# Copter_Transmitter.net
KiCad netlist of a schematic drawn in EAGLE
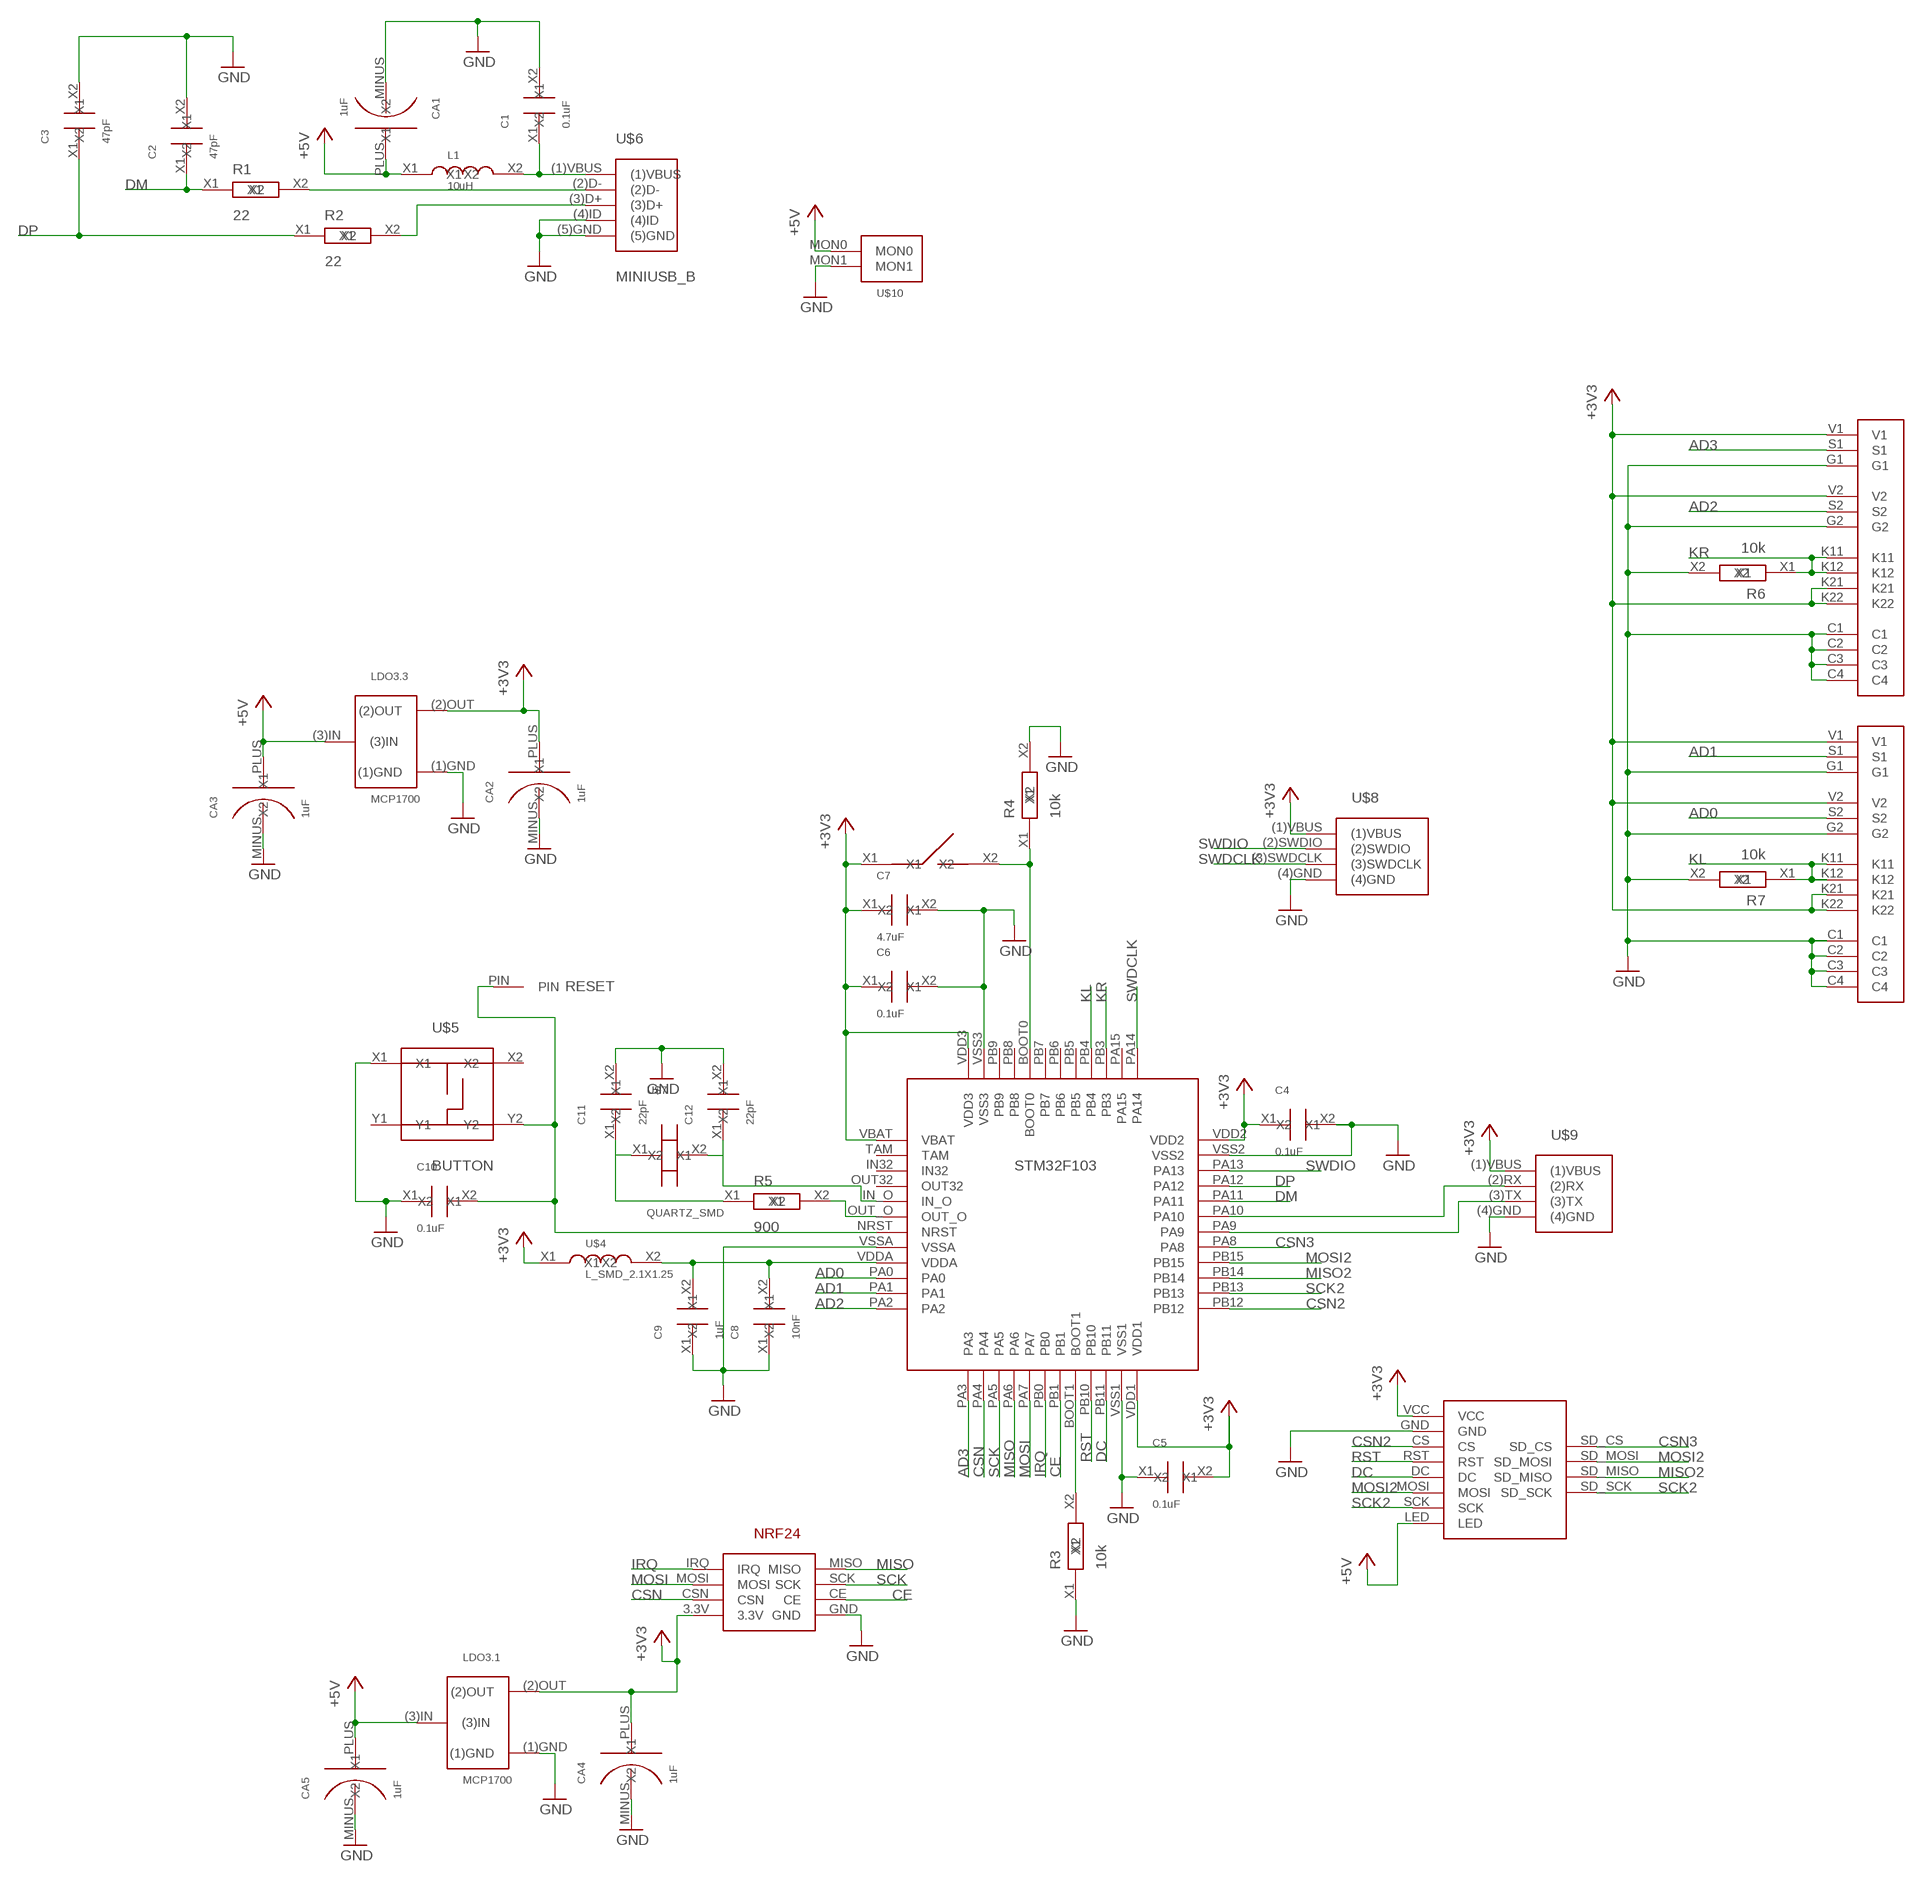
[diagram p0: schematic, sheet 1]

(export (version "E")
  (design (tool "Eeschema 10.0.6"))
  (components
    (comp (ref "C1")
      (value "0.1uF")
      (footprint "eagle-import:SMD_2.1X1.25")
      (libsource (lib "eagle-import") (part "C_SMD_2.1X1.25"))
    )
    (comp (ref "C2")
      (value "47pF")
      (footprint "eagle-import:SMD_2.1X1.25")
      (libsource (lib "eagle-import") (part "C_SMD_2.1X1.25"))
    )
    (comp (ref "C3")
      (value "47pF")
      (footprint "eagle-import:SMD_2.1X1.25")
      (libsource (lib "eagle-import") (part "C_SMD_2.1X1.25"))
    )
    (comp (ref "C4")
      (value "0.1uF")
      (footprint "eagle-import:SMD_2.1X1.25")
      (libsource (lib "eagle-import") (part "C_SMD_2.1X1.25"))
    )
    (comp (ref "C5")
      (value "0.1uF")
      (footprint "eagle-import:SMD_2.1X1.25")
      (libsource (lib "eagle-import") (part "C_SMD_2.1X1.25"))
    )
    (comp (ref "C6")
      (value "0.1uF")
      (footprint "eagle-import:SMD_2.1X1.25")
      (libsource (lib "eagle-import") (part "C_SMD_2.1X1.25"))
    )
    (comp (ref "C7")
      (value "4.7uF")
      (footprint "eagle-import:SMD_2.1X1.25")
      (libsource (lib "eagle-import") (part "C_SMD_2.1X1.25"))
    )
    (comp (ref "C8")
      (value "10nF")
      (footprint "eagle-import:SMD_2.1X1.25")
      (libsource (lib "eagle-import") (part "C_SMD_2.1X1.25"))
    )
    (comp (ref "C9")
      (value "1uF")
      (footprint "eagle-import:SMD_2.1X1.25")
      (libsource (lib "eagle-import") (part "C_SMD_2.1X1.25"))
    )
    (comp (ref "C10")
      (value "0.1uF")
      (footprint "eagle-import:SMD_2.1X1.25")
      (libsource (lib "eagle-import") (part "C_SMD_2.1X1.25"))
    )
    (comp (ref "C11")
      (value "22pF")
      (footprint "eagle-import:SMD_2.1X1.25")
      (libsource (lib "eagle-import") (part "C_SMD_2.1X1.25"))
    )
    (comp (ref "C12")
      (value "22pF")
      (footprint "eagle-import:SMD_2.1X1.25")
      (libsource (lib "eagle-import") (part "C_SMD_2.1X1.25"))
    )
    (comp (ref "CA1")
      (value "1uF")
      (footprint "eagle-import:C_SMD_TA_A")
      (libsource (lib "eagle-import") (part "C_SMD_TA_A"))
    )
    (comp (ref "CA2")
      (value "1uF")
      (footprint "eagle-import:C_SMD_TA_A")
      (libsource (lib "eagle-import") (part "C_SMD_TA_A"))
    )
    (comp (ref "CA3")
      (value "1uF")
      (footprint "eagle-import:C_SMD_TA_A")
      (libsource (lib "eagle-import") (part "C_SMD_TA_A"))
    )
    (comp (ref "CA4")
      (value "1uF")
      (footprint "eagle-import:C_SMD_TA_A")
      (libsource (lib "eagle-import") (part "C_SMD_TA_A"))
    )
    (comp (ref "CA5")
      (value "1uF")
      (footprint "eagle-import:C_SMD_TA_A")
      (libsource (lib "eagle-import") (part "C_SMD_TA_A"))
    )
    (comp (ref "L1")
      (value "10uH")
      (footprint "eagle-import:SMD_2.1X1.25")
      (libsource (lib "eagle-import") (part "L_SMD_2.1X1.25"))
    )
    (comp (ref "LDO3.1")
      (value "MCP1700")
      (footprint "eagle-import:MCP1700")
      (libsource (lib "eagle-import") (part "MCP1700"))
    )
    (comp (ref "LDO3.3")
      (value "MCP1700")
      (footprint "eagle-import:MCP1700")
      (libsource (lib "eagle-import") (part "MCP1700"))
    )
    (comp (ref "R1")
      (value "22")
      (footprint "eagle-import:SMD_2.1X1.25")
      (libsource (lib "eagle-import") (part "R_SMD_2.1X1.25"))
    )
    (comp (ref "R2")
      (value "22")
      (footprint "eagle-import:SMD_2.1X1.25")
      (libsource (lib "eagle-import") (part "R_SMD_2.1X1.25"))
    )
    (comp (ref "R3")
      (value "10k")
      (footprint "eagle-import:SMD_2.1X1.25")
      (libsource (lib "eagle-import") (part "R_SMD_2.1X1.25"))
    )
    (comp (ref "R4")
      (value "10k")
      (footprint "eagle-import:SMD_2.1X1.25")
      (libsource (lib "eagle-import") (part "R_SMD_2.1X1.25"))
    )
    (comp (ref "R5")
      (value "900")
      (footprint "eagle-import:SMD_2.1X1.25")
      (libsource (lib "eagle-import") (part "R_SMD_2.1X1.25"))
    )
    (comp (ref "R6")
      (value "10k")
      (footprint "eagle-import:SMD_2.1X1.25")
      (libsource (lib "eagle-import") (part "R_SMD_2.1X1.25"))
    )
    (comp (ref "R7")
      (value "10k")
      (footprint "eagle-import:SMD_2.1X1.25")
      (libsource (lib "eagle-import") (part "R_SMD_2.1X1.25"))
    )
    (comp (ref "RESET")
      (value "PIN")
      (footprint "eagle-import:PIN")
      (libsource (lib "eagle-import") (part "PIN"))
    )
    (comp (ref "STM32F103")
      (value "STM32F103CBT6")
      (footprint "eagle-import:STM32F103CBT6")
      (libsource (lib "eagle-import") (part "STM32F103CBT6"))
    )
    (comp (ref "U$1")
      (value "TFT1.8_SD")
      (footprint "eagle-import:TFT1.8_SD")
      (libsource (lib "eagle-import") (part "TFT1.8_SD"))
    )
    (comp (ref "U$2")
      (value "NRF24_PLUG")
      (footprint "eagle-import:NRF24_PLUG")
      (libsource (lib "eagle-import") (part "NRF24_PLUG"))
    )
    (comp (ref "U$3")
      (value "DIP_1")
      (footprint "eagle-import:DIP_1")
      (libsource (lib "eagle-import") (part "DIP_1"))
    )
    (comp (ref "U$4")
      (value "L_SMD_2.1X1.25")
      (footprint "eagle-import:SMD_2.1X1.25")
      (libsource (lib "eagle-import") (part "L_SMD_2.1X1.25"))
    )
    (comp (ref "U$5")
      (value "BUTTON")
      (footprint "eagle-import:BUTTON")
      (libsource (lib "eagle-import") (part "BUTTON"))
    )
    (comp (ref "U$6")
      (value "MINIUSB_B")
      (footprint "eagle-import:MINIUSB_B")
      (libsource (lib "eagle-import") (part "MINIUSB_B"))
    )
    (comp (ref "U$7")
      (value "QUARTZ_SMD")
      (footprint "eagle-import:QUARTZ_SMD")
      (libsource (lib "eagle-import") (part "QUARTZ_SMD"))
    )
    (comp (ref "U$8")
      (value "SWD")
      (footprint "eagle-import:SWD")
      (libsource (lib "eagle-import") (part "SWD"))
    )
    (comp (ref "U$9")
      (value "USART")
      (footprint "eagle-import:USART")
      (libsource (lib "eagle-import") (part "USART"))
    )
    (comp (ref "U$10")
      (value "MON2PIN")
      (footprint "eagle-import:MON2PIN")
      (libsource (lib "eagle-import") (part "MON2PIN"))
    )
    (comp (ref "U$11")
      (value "JOYSTICK_MINI")
      (footprint "eagle-import:JOYSTICK_MINI")
      (libsource (lib "eagle-import") (part "JOYSTICK_MINI"))
    )
    (comp (ref "U$12")
      (value "JOYSTICK_MINI")
      (footprint "eagle-import:JOYSTICK_MINI")
      (libsource (lib "eagle-import") (part "JOYSTICK_MINI"))
    )
  )
  (nets
    (net (code "1") (name "+3V3") (class "Default")
      (node (ref "C4") (pin "X1") (pinfunction "X1_X1") (pintype "bidirectional"))
      (node (ref "C5") (pin "X2") (pinfunction "X2_X2") (pintype "bidirectional"))
      (node (ref "C6") (pin "X1") (pinfunction "X1_X1") (pintype "bidirectional"))
      (node (ref "C7") (pin "X1") (pinfunction "X1_X1") (pintype "bidirectional"))
      (node (ref "CA2") (pin "PLUS") (pinfunction "X2_PLUS") (pintype "bidirectional"))
      (node (ref "CA4") (pin "PLUS") (pinfunction "X2_PLUS") (pintype "bidirectional"))
      (node (ref "LDO3.1") (pin "(2)OUT") (pinfunction "(2)OUT_(2)OUT") (pintype "bidirectional"))
      (node (ref "LDO3.3") (pin "(2)OUT") (pinfunction "(2)OUT_(2)OUT") (pintype "bidirectional"))
      (node (ref "STM32F103") (pin "VBAT") (pinfunction "VBAT_VBAT") (pintype "bidirectional"))
      (node (ref "STM32F103") (pin "VDD1") (pinfunction "VDD1_VDD1") (pintype "bidirectional"))
      (node (ref "STM32F103") (pin "VDD2") (pinfunction "VDD2_VDD2") (pintype "bidirectional"))
      (node (ref "STM32F103") (pin "VDD3") (pinfunction "VDD3_VDD3") (pintype "bidirectional"))
      (node (ref "U$1") (pin "VCC") (pinfunction "VCC_VCC") (pintype "bidirectional"))
      (node (ref "U$11") (pin "K21") (pinfunction "K21_K21") (pintype "bidirectional"))
      (node (ref "U$11") (pin "K22") (pinfunction "K22_K22") (pintype "bidirectional"))
      (node (ref "U$11") (pin "V1") (pinfunction "V1_V1") (pintype "bidirectional"))
      (node (ref "U$11") (pin "V2") (pinfunction "V2_V2") (pintype "bidirectional"))
      (node (ref "U$12") (pin "K21") (pinfunction "K21_K21") (pintype "bidirectional"))
      (node (ref "U$12") (pin "K22") (pinfunction "K22_K22") (pintype "bidirectional"))
      (node (ref "U$12") (pin "V1") (pinfunction "V1_V1") (pintype "bidirectional"))
      (node (ref "U$12") (pin "V2") (pinfunction "V2_V2") (pintype "bidirectional"))
      (node (ref "U$2") (pin "3.3V") (pinfunction "3.3V_3.3V") (pintype "bidirectional"))
      (node (ref "U$3") (pin "X1") (pinfunction "X1_X1") (pintype "bidirectional"))
      (node (ref "U$4") (pin "X1") (pinfunction "X1_X1") (pintype "bidirectional"))
      (node (ref "U$8") (pin "(1)VBUS") (pinfunction "(1)VBUS_(1)VBUS") (pintype "bidirectional"))
      (node (ref "U$9") (pin "(1)VBUS") (pinfunction "(1)VBUS_(1)VBUS") (pintype "bidirectional"))
    )
    (net (code "2") (name "+5V") (class "Default")
      (node (ref "CA1") (pin "PLUS") (pinfunction "X2_PLUS") (pintype "bidirectional"))
      (node (ref "CA3") (pin "PLUS") (pinfunction "X2_PLUS") (pintype "bidirectional"))
      (node (ref "CA5") (pin "PLUS") (pinfunction "X2_PLUS") (pintype "bidirectional"))
      (node (ref "L1") (pin "X1") (pinfunction "X1_X1") (pintype "bidirectional"))
      (node (ref "LDO3.1") (pin "(3)IN") (pinfunction "(3)IN_(3)IN") (pintype "bidirectional"))
      (node (ref "LDO3.3") (pin "(3)IN") (pinfunction "(3)IN_(3)IN") (pintype "bidirectional"))
      (node (ref "U$1") (pin "LED") (pinfunction "LED_LED") (pintype "bidirectional"))
      (node (ref "U$10") (pin "MON0") (pinfunction "MON0_MON0") (pintype "bidirectional"))
    )
    (net (code "3") (name "/AD0") (class "Default")
      (node (ref "STM32F103") (pin "PA0") (pinfunction "PA0_PA0") (pintype "bidirectional"))
      (node (ref "U$11") (pin "S2") (pinfunction "S2_S2") (pintype "bidirectional"))
    )
    (net (code "4") (name "/AD1") (class "Default")
      (node (ref "STM32F103") (pin "PA1") (pinfunction "PA1_PA1") (pintype "bidirectional"))
      (node (ref "U$11") (pin "S1") (pinfunction "S1_S1") (pintype "bidirectional"))
    )
    (net (code "5") (name "/AD2") (class "Default")
      (node (ref "STM32F103") (pin "PA2") (pinfunction "PA2_PA2") (pintype "bidirectional"))
      (node (ref "U$12") (pin "S2") (pinfunction "S2_S2") (pintype "bidirectional"))
    )
    (net (code "6") (name "/AD3") (class "Default")
      (node (ref "STM32F103") (pin "PA3") (pinfunction "PA3_PA3") (pintype "bidirectional"))
      (node (ref "U$12") (pin "S1") (pinfunction "S1_S1") (pintype "bidirectional"))
    )
    (net (code "7") (name "/CE") (class "Default")
      (node (ref "STM32F103") (pin "PB1") (pinfunction "PB1_PB1") (pintype "bidirectional"))
      (node (ref "U$2") (pin "CE") (pinfunction "CE_CE") (pintype "bidirectional"))
    )
    (net (code "8") (name "/CSN") (class "Default")
      (node (ref "STM32F103") (pin "PA4") (pinfunction "PA4_PA4") (pintype "bidirectional"))
      (node (ref "U$2") (pin "CSN") (pinfunction "CSN_CSN") (pintype "bidirectional"))
    )
    (net (code "9") (name "/CSN2") (class "Default")
      (node (ref "STM32F103") (pin "PB12") (pinfunction "PB12_PB12") (pintype "bidirectional"))
      (node (ref "U$1") (pin "CS") (pinfunction "CS_CS") (pintype "bidirectional"))
    )
    (net (code "10") (name "/CSN3") (class "Default")
      (node (ref "STM32F103") (pin "PA8") (pinfunction "PA8_PA8") (pintype "bidirectional"))
      (node (ref "U$1") (pin "SD_CS") (pinfunction "SD_CS_SD_CS") (pintype "bidirectional"))
    )
    (net (code "11") (name "/DC") (class "Default")
      (node (ref "STM32F103") (pin "PB11") (pinfunction "PB11_PB11") (pintype "bidirectional"))
      (node (ref "U$1") (pin "DC") (pinfunction "DC_DC") (pintype "bidirectional"))
    )
    (net (code "12") (name "/DM") (class "Default")
      (node (ref "C2") (pin "X1") (pinfunction "X1_X1") (pintype "bidirectional"))
      (node (ref "R1") (pin "X1") (pinfunction "X1_X1") (pintype "bidirectional"))
      (node (ref "STM32F103") (pin "PA11") (pinfunction "PA11_PA11") (pintype "bidirectional"))
    )
    (net (code "13") (name "/DP") (class "Default")
      (node (ref "C3") (pin "X1") (pinfunction "X1_X1") (pintype "bidirectional"))
      (node (ref "R2") (pin "X1") (pinfunction "X1_X1") (pintype "bidirectional"))
      (node (ref "STM32F103") (pin "PA12") (pinfunction "PA12_PA12") (pintype "bidirectional"))
    )
    (net (code "14") (name "/IRQ") (class "Default")
      (node (ref "STM32F103") (pin "PB0") (pinfunction "PB0_PB0") (pintype "bidirectional"))
      (node (ref "U$2") (pin "IRQ") (pinfunction "IRQ_IRQ") (pintype "bidirectional"))
    )
    (net (code "15") (name "/KL") (class "Default")
      (node (ref "R7") (pin "X1") (pinfunction "X1_X1") (pintype "bidirectional"))
      (node (ref "STM32F103") (pin "PB4") (pinfunction "PB4_PB4") (pintype "bidirectional"))
      (node (ref "U$11") (pin "K11") (pinfunction "K11_K11") (pintype "bidirectional"))
      (node (ref "U$11") (pin "K12") (pinfunction "K12_K12") (pintype "bidirectional"))
    )
    (net (code "16") (name "/KR") (class "Default")
      (node (ref "R6") (pin "X1") (pinfunction "X1_X1") (pintype "bidirectional"))
      (node (ref "STM32F103") (pin "PB3") (pinfunction "PB3_PB3") (pintype "bidirectional"))
      (node (ref "U$12") (pin "K11") (pinfunction "K11_K11") (pintype "bidirectional"))
      (node (ref "U$12") (pin "K12") (pinfunction "K12_K12") (pintype "bidirectional"))
    )
    (net (code "17") (name "/MISO") (class "Default")
      (node (ref "STM32F103") (pin "PA6") (pinfunction "PA6_PA6") (pintype "bidirectional"))
      (node (ref "U$2") (pin "MISO") (pinfunction "MISO_MISO") (pintype "bidirectional"))
    )
    (net (code "18") (name "/MISO2") (class "Default")
      (node (ref "STM32F103") (pin "PB14") (pinfunction "PB14_PB14") (pintype "bidirectional"))
      (node (ref "U$1") (pin "SD_MISO") (pinfunction "SD_MISO_SD_MISO") (pintype "bidirectional"))
    )
    (net (code "19") (name "/MOSI") (class "Default")
      (node (ref "STM32F103") (pin "PA7") (pinfunction "PA7_PA7") (pintype "bidirectional"))
      (node (ref "U$2") (pin "MOSI") (pinfunction "MOSI_MOSI") (pintype "bidirectional"))
    )
    (net (code "20") (name "/MOSI2") (class "Default")
      (node (ref "STM32F103") (pin "PB15") (pinfunction "PB15_PB15") (pintype "bidirectional"))
      (node (ref "U$1") (pin "MOSI") (pinfunction "MOSI_MOSI") (pintype "bidirectional"))
      (node (ref "U$1") (pin "SD_MOSI") (pinfunction "SD_MOSI_SD_MOSI") (pintype "bidirectional"))
    )
    (net (code "21") (name "/RST") (class "Default")
      (node (ref "STM32F103") (pin "PB10") (pinfunction "PB10_PB10") (pintype "bidirectional"))
      (node (ref "U$1") (pin "RST") (pinfunction "RST_RST") (pintype "bidirectional"))
    )
    (net (code "22") (name "/SCK") (class "Default")
      (node (ref "STM32F103") (pin "PA5") (pinfunction "PA5_PA5") (pintype "bidirectional"))
      (node (ref "U$2") (pin "SCK") (pinfunction "SCK_SCK") (pintype "bidirectional"))
    )
    (net (code "23") (name "/SCK2") (class "Default")
      (node (ref "STM32F103") (pin "PB13") (pinfunction "PB13_PB13") (pintype "bidirectional"))
      (node (ref "U$1") (pin "SCK") (pinfunction "SCK_SCK") (pintype "bidirectional"))
      (node (ref "U$1") (pin "SD_SCK") (pinfunction "SD_SCK_SD_SCK") (pintype "bidirectional"))
    )
    (net (code "24") (name "/SWDCLK") (class "Default")
      (node (ref "STM32F103") (pin "PA14") (pinfunction "PA14_PA14") (pintype "bidirectional"))
      (node (ref "U$8") (pin "(3)SWDCLK") (pinfunction "(3)SWDCLK_(3)SWDCLK") (pintype "bidirectional"))
    )
    (net (code "25") (name "/SWDIO") (class "Default")
      (node (ref "STM32F103") (pin "PA13") (pinfunction "PA13_PA13") (pintype "bidirectional"))
      (node (ref "U$8") (pin "(2)SWDIO") (pinfunction "(2)SWDIO_(2)SWDIO") (pintype "bidirectional"))
    )
    (net (code "26") (name "GND") (class "Default")
      (node (ref "C1") (pin "X2") (pinfunction "X2_X2") (pintype "bidirectional"))
      (node (ref "C10") (pin "X1") (pinfunction "X1_X1") (pintype "bidirectional"))
      (node (ref "C11") (pin "X2") (pinfunction "X2_X2") (pintype "bidirectional"))
      (node (ref "C12") (pin "X2") (pinfunction "X2_X2") (pintype "bidirectional"))
      (node (ref "C2") (pin "X2") (pinfunction "X2_X2") (pintype "bidirectional"))
      (node (ref "C3") (pin "X2") (pinfunction "X2_X2") (pintype "bidirectional"))
      (node (ref "C4") (pin "X2") (pinfunction "X2_X2") (pintype "bidirectional"))
      (node (ref "C5") (pin "X1") (pinfunction "X1_X1") (pintype "bidirectional"))
      (node (ref "C6") (pin "X2") (pinfunction "X2_X2") (pintype "bidirectional"))
      (node (ref "C7") (pin "X2") (pinfunction "X2_X2") (pintype "bidirectional"))
      (node (ref "C8") (pin "X1") (pinfunction "X1_X1") (pintype "bidirectional"))
      (node (ref "C9") (pin "X1") (pinfunction "X1_X1") (pintype "bidirectional"))
      (node (ref "CA1") (pin "MINUS") (pinfunction "X1_MINUS") (pintype "bidirectional"))
      (node (ref "CA2") (pin "MINUS") (pinfunction "X1_MINUS") (pintype "bidirectional"))
      (node (ref "CA3") (pin "MINUS") (pinfunction "X1_MINUS") (pintype "bidirectional"))
      (node (ref "CA4") (pin "MINUS") (pinfunction "X1_MINUS") (pintype "bidirectional"))
      (node (ref "CA5") (pin "MINUS") (pinfunction "X1_MINUS") (pintype "bidirectional"))
      (node (ref "LDO3.1") (pin "(1)GND") (pinfunction "(1)GND_(1)GND") (pintype "bidirectional"))
      (node (ref "LDO3.3") (pin "(1)GND") (pinfunction "(1)GND_(1)GND") (pintype "bidirectional"))
      (node (ref "R3") (pin "X1") (pinfunction "X1_X1") (pintype "bidirectional"))
      (node (ref "R4") (pin "X2") (pinfunction "X2_X2") (pintype "bidirectional"))
      (node (ref "R6") (pin "X2") (pinfunction "X2_X2") (pintype "bidirectional"))
      (node (ref "R7") (pin "X2") (pinfunction "X2_X2") (pintype "bidirectional"))
      (node (ref "STM32F103") (pin "VSS1") (pinfunction "VSS1_VSS1") (pintype "bidirectional"))
      (node (ref "STM32F103") (pin "VSS2") (pinfunction "VSS2_VSS2") (pintype "bidirectional"))
      (node (ref "STM32F103") (pin "VSS3") (pinfunction "VSS3_VSS3") (pintype "bidirectional"))
      (node (ref "STM32F103") (pin "VSSA") (pinfunction "VSSA_VSSA") (pintype "bidirectional"))
      (node (ref "U$1") (pin "GND") (pinfunction "GND_GND") (pintype "bidirectional"))
      (node (ref "U$10") (pin "MON1") (pinfunction "MON1_MON1") (pintype "bidirectional"))
      (node (ref "U$11") (pin "C1") (pinfunction "C1_C1") (pintype "bidirectional"))
      (node (ref "U$11") (pin "C2") (pinfunction "C2_C2") (pintype "bidirectional"))
      (node (ref "U$11") (pin "C3") (pinfunction "C3_C3") (pintype "bidirectional"))
      (node (ref "U$11") (pin "C4") (pinfunction "C4_C4") (pintype "bidirectional"))
      (node (ref "U$11") (pin "G1") (pinfunction "G1_G1") (pintype "bidirectional"))
      (node (ref "U$11") (pin "G2") (pinfunction "G2_G2") (pintype "bidirectional"))
      (node (ref "U$12") (pin "C1") (pinfunction "C1_C1") (pintype "bidirectional"))
      (node (ref "U$12") (pin "C2") (pinfunction "C2_C2") (pintype "bidirectional"))
      (node (ref "U$12") (pin "C3") (pinfunction "C3_C3") (pintype "bidirectional"))
      (node (ref "U$12") (pin "C4") (pinfunction "C4_C4") (pintype "bidirectional"))
      (node (ref "U$12") (pin "G1") (pinfunction "G1_G1") (pintype "bidirectional"))
      (node (ref "U$12") (pin "G2") (pinfunction "G2_G2") (pintype "bidirectional"))
      (node (ref "U$2") (pin "GND") (pinfunction "GND_GND") (pintype "bidirectional"))
      (node (ref "U$5") (pin "X1") (pinfunction "X1_X1") (pintype "bidirectional"))
      (node (ref "U$6") (pin "(4)ID") (pinfunction "(4)ID_(4)ID") (pintype "bidirectional"))
      (node (ref "U$6") (pin "(5)GND") (pinfunction "(5)GND_(5)GND") (pintype "bidirectional"))
      (node (ref "U$8") (pin "(4)GND") (pinfunction "(4)GND_(4)GND") (pintype "bidirectional"))
      (node (ref "U$9") (pin "(4)GND") (pinfunction "(4)GND_(4)GND") (pintype "bidirectional"))
    )
    (net (code "27") (name "Net-(C1-PadX1)") (class "Default")
      (node (ref "C1") (pin "X1") (pinfunction "X1_X1") (pintype "bidirectional"))
      (node (ref "L1") (pin "X2") (pinfunction "X2_X2") (pintype "bidirectional"))
      (node (ref "U$6") (pin "(1)VBUS") (pinfunction "(1)VBUS_(1)VBUS") (pintype "bidirectional"))
    )
    (net (code "28") (name "Net-(C8-PadX2)") (class "Default")
      (node (ref "C8") (pin "X2") (pinfunction "X2_X2") (pintype "bidirectional"))
      (node (ref "C9") (pin "X2") (pinfunction "X2_X2") (pintype "bidirectional"))
      (node (ref "STM32F103") (pin "VDDA") (pinfunction "VDDA_VDDA") (pintype "bidirectional"))
      (node (ref "U$4") (pin "X2") (pinfunction "X2_X2") (pintype "bidirectional"))
    )
    (net (code "29") (name "Net-(C10-PadX2)") (class "Default")
      (node (ref "C10") (pin "X2") (pinfunction "X2_X2") (pintype "bidirectional"))
      (node (ref "RESET") (pin "PIN") (pinfunction "PIN_PIN") (pintype "bidirectional"))
      (node (ref "STM32F103") (pin "NRST") (pinfunction "NRST_NRST") (pintype "bidirectional"))
      (node (ref "U$5") (pin "Y2") (pinfunction "Y2_Y2") (pintype "bidirectional"))
    )
    (net (code "30") (name "Net-(C11-PadX1)") (class "Default")
      (node (ref "C11") (pin "X1") (pinfunction "X1_X1") (pintype "bidirectional"))
      (node (ref "R5") (pin "X1") (pinfunction "X1_X1") (pintype "bidirectional"))
      (node (ref "U$7") (pin "X1") (pinfunction "X1_X1") (pintype "bidirectional"))
    )
    (net (code "31") (name "Net-(C12-PadX1)") (class "Default")
      (node (ref "C12") (pin "X1") (pinfunction "X1_X1") (pintype "bidirectional"))
      (node (ref "STM32F103") (pin "IN_O") (pinfunction "IN_O_IN_O") (pintype "bidirectional"))
      (node (ref "U$7") (pin "X2") (pinfunction "X2_X2") (pintype "bidirectional"))
    )
    (net (code "32") (name "Net-(R1-PadX2)") (class "Default")
      (node (ref "R1") (pin "X2") (pinfunction "X2_X2") (pintype "bidirectional"))
      (node (ref "U$6") (pin "(2)D-") (pinfunction "(2)D-_(2)D-") (pintype "bidirectional"))
    )
    (net (code "33") (name "Net-(R2-PadX2)") (class "Default")
      (node (ref "R2") (pin "X2") (pinfunction "X2_X2") (pintype "bidirectional"))
      (node (ref "U$6") (pin "(3)D+") (pinfunction "(3)D+_(3)D+") (pintype "bidirectional"))
    )
    (net (code "34") (name "Net-(R3-PadX2)") (class "Default")
      (node (ref "R3") (pin "X2") (pinfunction "X2_X2") (pintype "bidirectional"))
      (node (ref "STM32F103") (pin "BOOT1") (pinfunction "BOOT1_BOOT1") (pintype "bidirectional"))
    )
    (net (code "35") (name "Net-(R4-PadX1)") (class "Default")
      (node (ref "R4") (pin "X1") (pinfunction "X1_X1") (pintype "bidirectional"))
      (node (ref "STM32F103") (pin "BOOT0") (pinfunction "BOOT0_BOOT0") (pintype "bidirectional"))
      (node (ref "U$3") (pin "X2") (pinfunction "X2_X2") (pintype "bidirectional"))
    )
    (net (code "36") (name "Net-(R5-PadX2)") (class "Default")
      (node (ref "R5") (pin "X2") (pinfunction "X2_X2") (pintype "bidirectional"))
      (node (ref "STM32F103") (pin "OUT_O") (pinfunction "OUT_O_OUT_O") (pintype "bidirectional"))
    )
    (net (code "37") (name "Net-(STM32F103-PadPA9)") (class "Default")
      (node (ref "STM32F103") (pin "PA9") (pinfunction "PA9_PA9") (pintype "bidirectional"))
      (node (ref "U$9") (pin "(3)TX") (pinfunction "(3)TX_(3)TX") (pintype "bidirectional"))
    )
    (net (code "38") (name "Net-(STM32F103-PadPA10)") (class "Default")
      (node (ref "STM32F103") (pin "PA10") (pinfunction "PA10_PA10") (pintype "bidirectional"))
      (node (ref "U$9") (pin "(2)RX") (pinfunction "(2)RX_(2)RX") (pintype "bidirectional"))
    )
    (net (code "39") (name "unconnected-(STM32F103-PadIN32)") (class "Default")
      (node (ref "STM32F103") (pin "IN32") (pinfunction "IN32_IN32") (pintype "bidirectional"))
    )
    (net (code "40") (name "unconnected-(STM32F103-PadOUT32)") (class "Default")
      (node (ref "STM32F103") (pin "OUT32") (pinfunction "OUT32_OUT32") (pintype "bidirectional"))
    )
    (net (code "41") (name "unconnected-(STM32F103-PadPA15)") (class "Default")
      (node (ref "STM32F103") (pin "PA15") (pinfunction "PA15_PA15") (pintype "bidirectional"))
    )
    (net (code "42") (name "unconnected-(STM32F103-PadPB5)") (class "Default")
      (node (ref "STM32F103") (pin "PB5") (pinfunction "PB5_PB5") (pintype "bidirectional"))
    )
    (net (code "43") (name "unconnected-(STM32F103-PadPB6)") (class "Default")
      (node (ref "STM32F103") (pin "PB6") (pinfunction "PB6_PB6") (pintype "bidirectional"))
    )
    (net (code "44") (name "unconnected-(STM32F103-PadPB7)") (class "Default")
      (node (ref "STM32F103") (pin "PB7") (pinfunction "PB7_PB7") (pintype "bidirectional"))
    )
    (net (code "45") (name "unconnected-(STM32F103-PadPB8)") (class "Default")
      (node (ref "STM32F103") (pin "PB8") (pinfunction "PB8_PB8") (pintype "bidirectional"))
    )
    (net (code "46") (name "unconnected-(STM32F103-PadPB9)") (class "Default")
      (node (ref "STM32F103") (pin "PB9") (pinfunction "PB9_PB9") (pintype "bidirectional"))
    )
    (net (code "47") (name "unconnected-(STM32F103-PadTAM)") (class "Default")
      (node (ref "STM32F103") (pin "TAM") (pinfunction "TAM_TAM") (pintype "bidirectional"))
    )
    (net (code "48") (name "unconnected-(U$5-PadX2)") (class "Default")
      (node (ref "U$5") (pin "X2") (pinfunction "X2_X2") (pintype "bidirectional"))
    )
    (net (code "49") (name "unconnected-(U$5-PadY1)") (class "Default")
      (node (ref "U$5") (pin "Y1") (pinfunction "Y1_Y1") (pintype "bidirectional"))
    )
  )
)
